# BuckConverter.net
KiCad netlist of a schematic drawn in Altium Designer
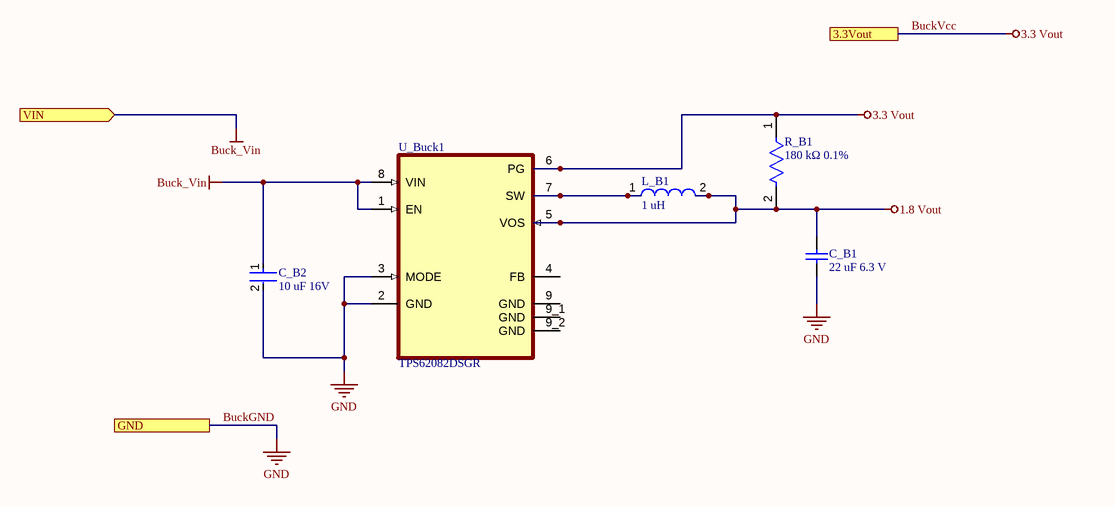
[diagram p0: BuckConverter.SchDoc]

(export (version "E")
  (design (tool "Eeschema 10.0.6"))
  (components
    (comp (ref "C_B1")
      (value "22 uF 6.3 V")
      (footprint "CAPC1608X100X20ML10")
      (description "Chip Capacitor, 22 uF, +/- 20%, 6.3 V, -55 to 85 degC, 1608 (0603 Metric), RoHS, Tape and Reel")
      (fields
        (field (name "TOLERANCE") "±20%")
        (field (name "PCN PART NUMBER") "MLCCPartNumberChange30/Nov/2012")
      )
      (libsource (lib "Altium Content Vault") (part "CAP-NP-2"))
    )
    (comp (ref "C_B2")
      (value "10 uF 16V")
      (footprint "FP-C1608-MFG")
      (description "CAP CER 10UF 16V X5R 0603")
      (fields
        (field (name "OCTOPART") "https://octopart.com/c1608x5r1c106m080ab-tdk-26013480")
        (field (name "MANUFACTURER") "TDK Corporation")
      )
      (libsource (lib "Altium Content Vault") (part "11868f565c42a9108669ba33697ecf6"))
    )
    (comp (ref "L_B1")
      (value "1 uH")
      (footprint "WE-HCI-7040")
      (description "744311100 SMD Flat Wire High Current Inductor WE-HCI, L=1.00 µH")
      (libsource (lib "Altium Content Vault") (part "PAS-IND-INDUCTOR-2"))
    )
    (comp (ref "R_B1")
      (value "180 kΩ 0.1%")
      (footprint "FP-CPF0603-MFG")
      (description "RES SMD 180KΩ 0.1% 1/16W 0603")
      (fields
        (field (name "OCTOPART") "https://octopart.com/cpf0603b180ke-te+connectivity-23257790")
        (field (name "TOLERANCE") "0.1%")
      )
      (libsource (lib "Altium Content Vault") (part "1029c3af85768c4190bb7ad29bc67b5"))
    )
    (comp (ref "U_Buck1")
      (value "TPS62082DSGR")
      (footprint "SON50P200X200X80-9N")
      (description "1.2A High Efficient Step Down Converter in 2x2mm SON Package. 3.3 Vout (Min) 8-WSON -40 to 125")
      (fields (field (name "MF") "Texas Instruments") (field (name "DIGI-KEY_PART_NUMBER") "296-49331-1-ND"))
      (libsource (lib "TPS62082DSGR") (part "TPS62082DSGR"))
    )
  )
  (nets
    (net (code "1") (name "1.8 Vout") (class "Default")
      (node (ref "C_B1") (pin "2") (pinfunction "2_2") (pintype "passive"))
      (node (ref "L_B1") (pin "2") (pinfunction "2_2") (pintype "passive"))
      (node (ref "R_B1") (pin "2") (pinfunction "2_2") (pintype "passive"))
      (node (ref "U_Buck1") (pin "5") (pinfunction "VOS_5") (pintype "input"))
    )
    (net (code "2") (name "3.3 Vout") (class "Default")
      (node (ref "R_B1") (pin "1") (pinfunction "1_1") (pintype "passive"))
      (node (ref "U_Buck1") (pin "6") (pinfunction "PG_6") (pintype "passive"))
    )
    (net (code "3") (name "Buck_Vin") (class "Default")
      (node (ref "C_B2") (pin "1") (pinfunction "1_1") (pintype "passive"))
      (node (ref "U_Buck1") (pin "1") (pinfunction "EN_1") (pintype "input"))
      (node (ref "U_Buck1") (pin "8") (pinfunction "VIN_8") (pintype "input"))
    )
    (net (code "4") (name "GND") (class "Default")
      (node (ref "C_B1") (pin "1") (pinfunction "1_1") (pintype "passive"))
      (node (ref "C_B2") (pin "2") (pinfunction "2_2") (pintype "passive"))
      (node (ref "U_Buck1") (pin "2") (pinfunction "GND_2") (pintype "power_in"))
      (node (ref "U_Buck1") (pin "3") (pinfunction "MODE_3") (pintype "input"))
    )
    (net (code "5") (name "Net-(U_Buck1-SW)") (class "Default")
      (node (ref "L_B1") (pin "1") (pinfunction "1_1") (pintype "passive"))
      (node (ref "U_Buck1") (pin "7") (pinfunction "SW_7") (pintype "power_in"))
    )
    (net (code "6") (name "unconnected-(U_Buck1-FB-Pad4)") (class "Default")
      (node (ref "U_Buck1") (pin "4") (pinfunction "FB_4") (pintype "passive"))
    )
    (net (code "7") (name "unconnected-(U_Buck1-GND-Pad9)") (class "Default")
      (node (ref "U_Buck1") (pin "9") (pinfunction "GND_9") (pintype "power_in"))
    )
    (net (code "8") (name "unconnected-(U_Buck1-GND-Pad9_1)") (class "Default")
      (node (ref "U_Buck1") (pin "9_1") (pinfunction "GND_9_1") (pintype "power_in"))
    )
    (net (code "9") (name "unconnected-(U_Buck1-GND-Pad9_2)") (class "Default")
      (node (ref "U_Buck1") (pin "9_2") (pinfunction "GND_9_2") (pintype "power_in"))
    )
  )
)
